# Activity_Recognition_Board_v1_0_MCU.net
KiCad netlist of a schematic drawn in Altium Designer
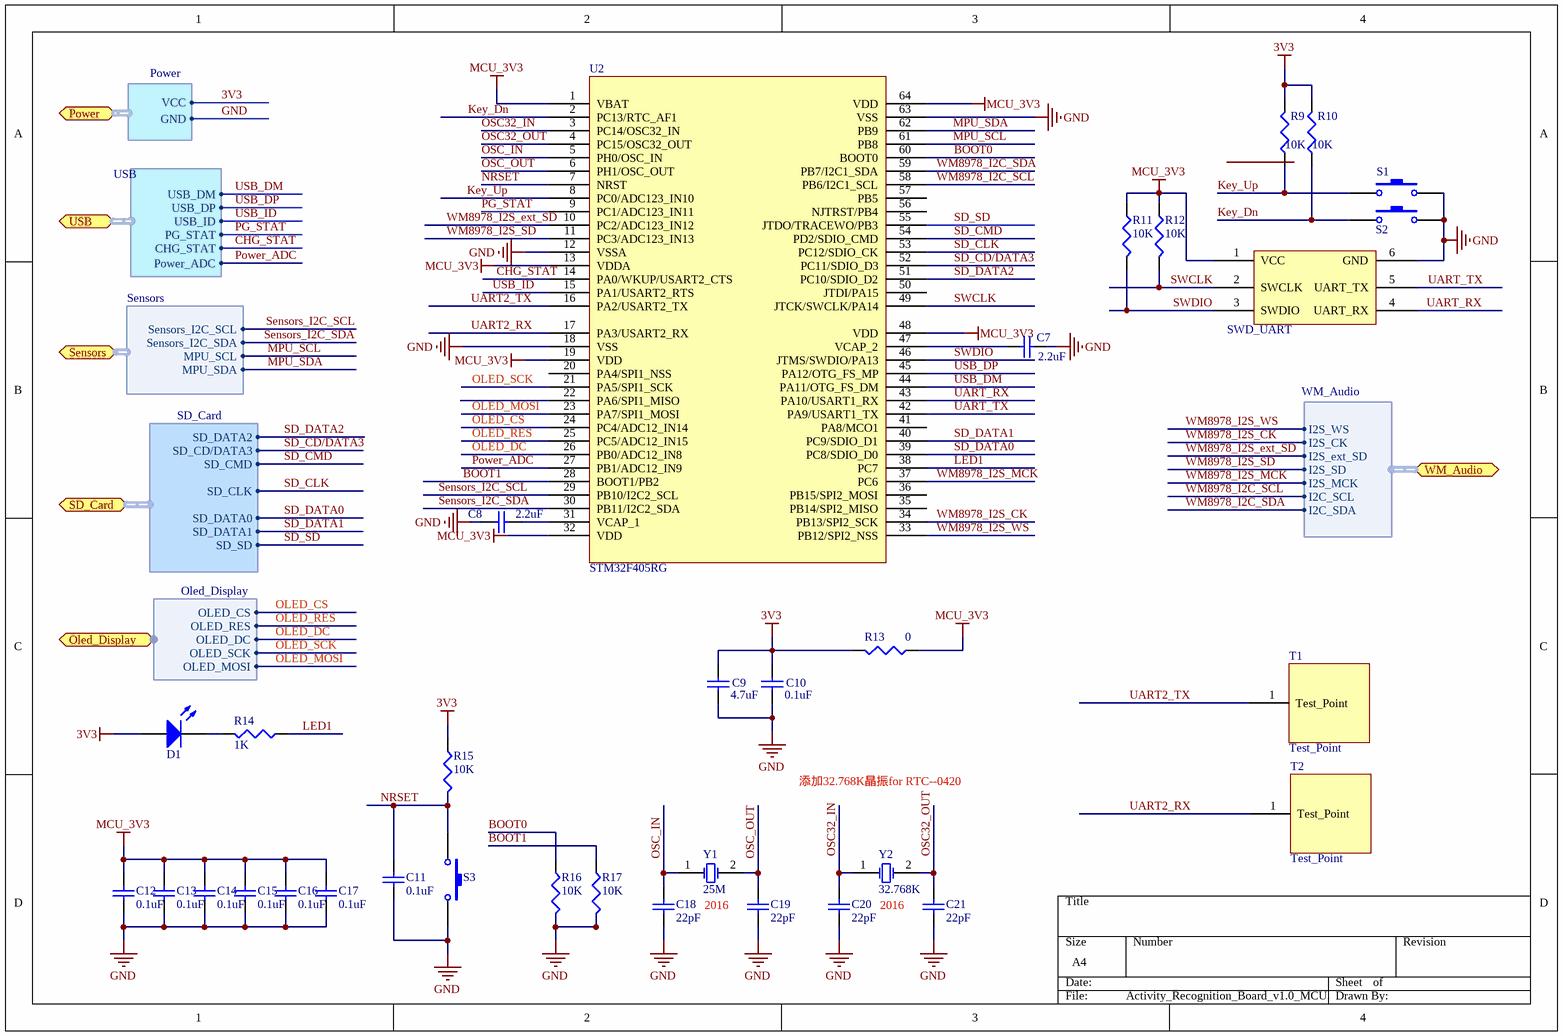
[diagram p0: Activity_Recognition_Board_v1.0_MCU.SchDoc]

(export (version "E")
  (design (tool "Eeschema 10.0.6"))
  (components
    (comp (ref "C7")
      (value "2.2uF")
      (footprint "C0603")
      (description "Capacitor (Semiconductor SIM Model)")
      (fields (field (name "Comment") "Cap semi") (field (name "PUBLISHER") "Altium Limited"))
      (libsource (lib "Miscellaneous Devices") (part "Cap Semi"))
    )
    (comp (ref "C8")
      (value "2.2uF")
      (footprint "C0603")
      (description "Capacitor (Semiconductor SIM Model)")
      (fields (field (name "Comment") "Cap semi") (field (name "PUBLISHER") "Altium Limited"))
      (libsource (lib "Miscellaneous Devices") (part "Cap Semi"))
    )
    (comp (ref "C9")
      (value "4.7uF")
      (footprint "C0603")
      (description "Capacitor (Semiconductor SIM Model)")
      (fields (field (name "Comment") "Cap semi") (field (name "PUBLISHER") "Altium Limited"))
      (libsource (lib "Miscellaneous Devices") (part "Cap Semi"))
    )
    (comp (ref "C10")
      (value "0.1uF")
      (footprint "C0402")
      (description "Capacitor (Semiconductor SIM Model)")
      (fields (field (name "Comment") "Cap semi") (field (name "PUBLISHER") "Altium Limited"))
      (libsource (lib "Miscellaneous Devices") (part "Cap Semi"))
    )
    (comp (ref "C11")
      (value "0.1uF")
      (footprint "C0402")
      (description "Capacitor (Semiconductor SIM Model)")
      (fields (field (name "Comment") "Cap semi") (field (name "PUBLISHER") "Altium Limited"))
      (libsource (lib "Miscellaneous Devices") (part "Cap Semi"))
    )
    (comp (ref "C12")
      (value "0.1uF")
      (footprint "C0402")
      (description "Capacitor (Semiconductor SIM Model)")
      (fields (field (name "Comment") "Cap semi") (field (name "PUBLISHER") "Altium Limited"))
      (libsource (lib "Miscellaneous Devices") (part "Cap Semi"))
    )
    (comp (ref "C13")
      (value "0.1uF")
      (footprint "C0402")
      (description "Capacitor (Semiconductor SIM Model)")
      (fields (field (name "Comment") "Cap semi") (field (name "PUBLISHER") "Altium Limited"))
      (libsource (lib "Miscellaneous Devices") (part "Cap Semi"))
    )
    (comp (ref "C14")
      (value "0.1uF")
      (footprint "C0402")
      (description "Capacitor (Semiconductor SIM Model)")
      (fields (field (name "Comment") "Cap semi") (field (name "PUBLISHER") "Altium Limited"))
      (libsource (lib "Miscellaneous Devices") (part "Cap Semi"))
    )
    (comp (ref "C15")
      (value "0.1uF")
      (footprint "C0402")
      (description "Capacitor (Semiconductor SIM Model)")
      (fields (field (name "Comment") "Cap semi") (field (name "PUBLISHER") "Altium Limited"))
      (libsource (lib "Miscellaneous Devices") (part "Cap Semi"))
    )
    (comp (ref "C16")
      (value "0.1uF")
      (footprint "C0402")
      (description "Capacitor (Semiconductor SIM Model)")
      (fields (field (name "Comment") "Cap semi") (field (name "PUBLISHER") "Altium Limited"))
      (libsource (lib "Miscellaneous Devices") (part "Cap Semi"))
    )
    (comp (ref "C17")
      (value "0.1uF")
      (footprint "C0402")
      (description "Capacitor (Semiconductor SIM Model)")
      (fields (field (name "Comment") "Cap semi") (field (name "PUBLISHER") "Altium Limited"))
      (libsource (lib "Miscellaneous Devices") (part "Cap Semi"))
    )
    (comp (ref "C18")
      (value "22pF")
      (footprint "C0402")
      (description "Capacitor (Semiconductor SIM Model)")
      (fields (field (name "Comment") "Cap semi") (field (name "PUBLISHER") "Altium Limited"))
      (libsource (lib "Miscellaneous Devices") (part "Cap Semi"))
    )
    (comp (ref "C19")
      (value "22pF")
      (footprint "C0402")
      (description "Capacitor (Semiconductor SIM Model)")
      (fields (field (name "Comment") "Cap semi") (field (name "PUBLISHER") "Altium Limited"))
      (libsource (lib "Miscellaneous Devices") (part "Cap Semi"))
    )
    (comp (ref "C20")
      (value "22pF")
      (footprint "C0402")
      (description "Capacitor (Semiconductor SIM Model)")
      (fields (field (name "Comment") "Cap semi") (field (name "PUBLISHER") "Altium Limited"))
      (libsource (lib "Miscellaneous Devices") (part "Cap Semi"))
    )
    (comp (ref "C21")
      (value "22pF")
      (footprint "C0402")
      (description "Capacitor (Semiconductor SIM Model)")
      (fields (field (name "Comment") "Cap semi") (field (name "PUBLISHER") "Altium Limited"))
      (libsource (lib "Miscellaneous Devices") (part "Cap Semi"))
    )
    (comp (ref "D1")
      (value "LED3")
      (footprint "LED0603")
      (description "Typical BLUE SiC LED")
      (fields (field (name "PUBLISHER") "Altium Limited"))
      (libsource (lib "Miscellaneous Devices") (part "LED3"))
    )
    (comp (ref "R9")
      (value "10K")
      (footprint "R0402")
      (description "Resistor")
      (fields (field (name "Comment") "Res3") (field (name "PUBLISHER") "Altium Limited"))
      (libsource (lib "Miscellaneous Devices") (part "Res3"))
    )
    (comp (ref "R10")
      (value "10K")
      (footprint "R0402")
      (description "Resistor")
      (fields (field (name "Comment") "Res3") (field (name "PUBLISHER") "Altium Limited"))
      (libsource (lib "Miscellaneous Devices") (part "Res3"))
    )
    (comp (ref "R11")
      (value "10K")
      (footprint "R0402")
      (description "Resistor")
      (fields (field (name "Comment") "Res3") (field (name "PUBLISHER") "Altium Limited"))
      (libsource (lib "Miscellaneous Devices") (part "Res3"))
    )
    (comp (ref "R12")
      (value "10K")
      (footprint "R0402")
      (description "Resistor")
      (fields (field (name "Comment") "Res3") (field (name "PUBLISHER") "Altium Limited"))
      (libsource (lib "Miscellaneous Devices") (part "Res3"))
    )
    (comp (ref "R13")
      (value "0")
      (footprint "R0603")
      (description "Resistor")
      (fields (field (name "Comment") "Res3") (field (name "PUBLISHER") "Altium Limited"))
      (libsource (lib "Miscellaneous Devices") (part "Res3"))
    )
    (comp (ref "R14")
      (value "1K")
      (footprint "R0402")
      (description "Resistor")
      (fields (field (name "Comment") "Res3") (field (name "PUBLISHER") "Altium Limited"))
      (libsource (lib "Miscellaneous Devices") (part "Res3"))
    )
    (comp (ref "R15")
      (value "10K")
      (footprint "R0402")
      (description "Resistor")
      (fields (field (name "Comment") "Res3") (field (name "PUBLISHER") "Altium Limited"))
      (libsource (lib "Miscellaneous Devices") (part "Res3"))
    )
    (comp (ref "R16")
      (value "10K")
      (footprint "R0402")
      (description "Resistor")
      (fields (field (name "Comment") "Res3") (field (name "PUBLISHER") "Altium Limited"))
      (libsource (lib "Miscellaneous Devices") (part "Res3"))
    )
    (comp (ref "R17")
      (value "10K")
      (footprint "R0402")
      (description "Resistor")
      (fields (field (name "Comment") "Res3") (field (name "PUBLISHER") "Altium Limited"))
      (libsource (lib "Miscellaneous Devices") (part "Res3"))
    )
    (comp (ref "S1")
      (value "SW-PB")
      (footprint "MP34")
      (description "Switch")
      (fields (field (name "PUBLISHER") "Altium Limited"))
      (libsource (lib "Miscellaneous Devices") (part "SW-PB"))
    )
    (comp (ref "S2")
      (value "SW-PB")
      (footprint "MP34")
      (description "Switch")
      (fields (field (name "PUBLISHER") "Altium Limited"))
      (libsource (lib "Miscellaneous Devices") (part "SW-PB"))
    )
    (comp (ref "S3")
      (value "SW-PB")
      (footprint "MP34")
      (description "Switch")
      (fields (field (name "PUBLISHER") "Altium Limited"))
      (libsource (lib "Miscellaneous Devices") (part "SW-PB"))
    )
    (comp (ref "SWD_UART1")
      (value "SWD_UART")
      (footprint "FFC_6")
      (libsource (lib "Activity_Recognition_Board") (part "SWD_UART"))
    )
    (comp (ref "T1")
      (value "Test_Point")
      (footprint "Test_Point")
      (libsource (lib "Activity_Recognition_Board") (part "Test_Point"))
    )
    (comp (ref "T2")
      (value "Test_Point")
      (footprint "Test_Point")
      (libsource (lib "Activity_Recognition_Board") (part "Test_Point"))
    )
    (comp (ref "U2")
      (value "STM32F405RG")
      (footprint "LQFP64")
      (libsource (lib "Schlib1_GuJun") (part "STM32F405RG"))
    )
    (comp (ref "Y1")
      (value "25M")
      (footprint "3225")
      (description "Crystal Oscillator")
      (fields (field (name "PUBLISHER") "Altium Limited"))
      (libsource (lib "Miscellaneous Devices") (part "XTAL"))
    )
    (comp (ref "Y2")
      (value "32.768K")
      (footprint "3215")
      (description "Crystal Oscillator")
      (fields (field (name "PUBLISHER") "Altium Limited"))
      (libsource (lib "Miscellaneous Devices") (part "XTAL"))
    )
  )
  (nets
    (net (code "7") (name "/BOOT0") (class "Default")
      (node (ref "R16") (pin "1") (pinfunction "1_1") (pintype "passive"))
      (node (ref "U2") (pin "60") (pinfunction "BOOT0_60") (pintype "passive"))
    )
    (net (code "8") (name "/BOOT1") (class "Default")
      (node (ref "R17") (pin "1") (pinfunction "1_1") (pintype "passive"))
      (node (ref "U2") (pin "28") (pinfunction "BOOT1/PB2_28") (pintype "passive"))
    )
    (net (code "9") (name "/CHG_STAT") (class "Default")
      (node (ref "U2") (pin "14") (pinfunction "PA0/WKUP/USART2_CTS_14") (pintype "passive"))
    )
    (net (code "10") (name "/Key_Dn") (class "Default")
      (node (ref "R10") (pin "1") (pinfunction "1_1") (pintype "passive"))
      (node (ref "S2") (pin "1") (pinfunction "1_1") (pintype "passive"))
      (node (ref "U2") (pin "2") (pinfunction "PC13/RTC_AF1_2") (pintype "passive"))
    )
    (net (code "11") (name "/Key_Up") (class "Default")
      (node (ref "R9") (pin "1") (pinfunction "1_1") (pintype "passive"))
      (node (ref "S1") (pin "1") (pinfunction "1_1") (pintype "passive"))
      (node (ref "U2") (pin "8") (pinfunction "PC0/ADC123_IN10_8") (pintype "passive"))
    )
    (net (code "12") (name "/LED1") (class "Default")
      (node (ref "R14") (pin "1") (pinfunction "1_1") (pintype "passive"))
      (node (ref "U2") (pin "38") (pinfunction "PC7_38") (pintype "passive"))
    )
    (net (code "13") (name "/MPU_SCL") (class "Default")
      (node (ref "U2") (pin "61") (pinfunction "PB8_61") (pintype "passive"))
    )
    (net (code "14") (name "/MPU_SDA") (class "Default")
      (node (ref "U2") (pin "62") (pinfunction "PB9_62") (pintype "passive"))
    )
    (net (code "15") (name "/NRSET") (class "Default")
      (node (ref "C11") (pin "2") (pinfunction "2_2") (pintype "passive"))
      (node (ref "R15") (pin "2") (pinfunction "2_2") (pintype "passive"))
      (node (ref "S3") (pin "1") (pinfunction "1_1") (pintype "passive"))
      (node (ref "U2") (pin "7") (pinfunction "NRST_7") (pintype "passive"))
    )
    (net (code "16") (name "/OLED_CS") (class "Default")
      (node (ref "U2") (pin "24") (pinfunction "PC4/ADC12_IN14_24") (pintype "passive"))
    )
    (net (code "17") (name "/OLED_DC") (class "Default")
      (node (ref "U2") (pin "26") (pinfunction "PB0/ADC12_IN8_26") (pintype "passive"))
    )
    (net (code "18") (name "/OLED_MOSI") (class "Default")
      (node (ref "U2") (pin "23") (pinfunction "PA7/SPI1_MOSI_23") (pintype "passive"))
    )
    (net (code "19") (name "/OLED_RES") (class "Default")
      (node (ref "U2") (pin "25") (pinfunction "PC5/ADC12_IN15_25") (pintype "passive"))
    )
    (net (code "20") (name "/OLED_SCK") (class "Default")
      (node (ref "U2") (pin "21") (pinfunction "PA5/SPI1_SCK_21") (pintype "passive"))
    )
    (net (code "21") (name "/OSC32_IN") (class "Default")
      (node (ref "C20") (pin "2") (pinfunction "2_2") (pintype "passive"))
      (node (ref "U2") (pin "3") (pinfunction "PC14/OSC32_IN_3") (pintype "passive"))
      (node (ref "Y2") (pin "1") (pinfunction "OSC1_1") (pintype "passive"))
    )
    (net (code "22") (name "/OSC32_OUT") (class "Default")
      (node (ref "C21") (pin "2") (pinfunction "2_2") (pintype "passive"))
      (node (ref "U2") (pin "4") (pinfunction "PC15/OSC32_OUT_4") (pintype "passive"))
      (node (ref "Y2") (pin "2") (pinfunction "OSC2_2") (pintype "passive"))
    )
    (net (code "23") (name "/OSC_IN") (class "Default")
      (node (ref "C18") (pin "2") (pinfunction "2_2") (pintype "passive"))
      (node (ref "U2") (pin "5") (pinfunction "PH0/OSC_IN_5") (pintype "passive"))
      (node (ref "Y1") (pin "1") (pinfunction "OSC1_1") (pintype "passive"))
    )
    (net (code "24") (name "/OSC_OUT") (class "Default")
      (node (ref "C19") (pin "2") (pinfunction "2_2") (pintype "passive"))
      (node (ref "U2") (pin "6") (pinfunction "PH1/OSC_OUT_6") (pintype "passive"))
      (node (ref "Y1") (pin "2") (pinfunction "OSC2_2") (pintype "passive"))
    )
    (net (code "25") (name "/PG_STAT") (class "Default")
      (node (ref "U2") (pin "9") (pinfunction "PC1/ADC123_IN11_9") (pintype "passive"))
    )
    (net (code "26") (name "/Power_ADC") (class "Default")
      (node (ref "U2") (pin "27") (pinfunction "PB1/ADC12_IN9_27") (pintype "passive"))
    )
    (net (code "27") (name "/SD_CD{slash}DATA3") (class "Default")
      (node (ref "U2") (pin "52") (pinfunction "PC11/SDIO_D3_52") (pintype "passive"))
    )
    (net (code "28") (name "/SD_CLK") (class "Default")
      (node (ref "U2") (pin "53") (pinfunction "PC12/SDIO_CK_53") (pintype "passive"))
    )
    (net (code "29") (name "/SD_CMD") (class "Default")
      (node (ref "U2") (pin "54") (pinfunction "PD2/SDIO_CMD_54") (pintype "passive"))
    )
    (net (code "30") (name "/SD_DATA0") (class "Default")
      (node (ref "U2") (pin "39") (pinfunction "PC8/SDIO_D0_39") (pintype "passive"))
    )
    (net (code "31") (name "/SD_DATA1") (class "Default")
      (node (ref "U2") (pin "40") (pinfunction "PC9/SDIO_D1_40") (pintype "passive"))
    )
    (net (code "32") (name "/SD_DATA2") (class "Default")
      (node (ref "U2") (pin "51") (pinfunction "PC10/SDIO_D2_51") (pintype "passive"))
    )
    (net (code "33") (name "/SD_SD") (class "Default")
      (node (ref "U2") (pin "55") (pinfunction "JTDO/TRACEWO/PB3_55") (pintype "passive"))
    )
    (net (code "34") (name "/SWCLK") (class "Default")
      (node (ref "R12") (pin "2") (pinfunction "2_2") (pintype "passive"))
      (node (ref "SWD_UART1") (pin "2") (pinfunction "SWCLK_2") (pintype "passive"))
      (node (ref "U2") (pin "49") (pinfunction "JTCK/SWCLK/PA14_49") (pintype "passive"))
    )
    (net (code "35") (name "/SWDIO") (class "Default")
      (node (ref "R11") (pin "2") (pinfunction "2_2") (pintype "passive"))
      (node (ref "SWD_UART1") (pin "3") (pinfunction "SWDIO_3") (pintype "passive"))
      (node (ref "U2") (pin "46") (pinfunction "JTMS/SWDIO/PA13_46") (pintype "passive"))
    )
    (net (code "36") (name "/Sensors_I2C_SCL") (class "Default")
      (node (ref "U2") (pin "29") (pinfunction "PB10/I2C2_SCL_29") (pintype "passive"))
    )
    (net (code "37") (name "/Sensors_I2C_SDA") (class "Default")
      (node (ref "U2") (pin "30") (pinfunction "PB11/I2C2_SDA_30") (pintype "passive"))
    )
    (net (code "38") (name "/UART2_RX") (class "Default")
      (node (ref "T2") (pin "1") (pinfunction "Test_Point_1") (pintype "passive"))
      (node (ref "U2") (pin "17") (pinfunction "PA3/USART2_RX_17") (pintype "passive"))
    )
    (net (code "39") (name "/UART2_TX") (class "Default")
      (node (ref "T1") (pin "1") (pinfunction "Test_Point_1") (pintype "passive"))
      (node (ref "U2") (pin "16") (pinfunction "PA2/USART2_TX_16") (pintype "passive"))
    )
    (net (code "40") (name "/UART_RX") (class "Default")
      (node (ref "SWD_UART1") (pin "4") (pinfunction "UART_RX_4") (pintype "passive"))
      (node (ref "U2") (pin "43") (pinfunction "PA10/USART1_RX_43") (pintype "passive"))
    )
    (net (code "41") (name "/UART_TX") (class "Default")
      (node (ref "SWD_UART1") (pin "5") (pinfunction "UART_TX_5") (pintype "passive"))
      (node (ref "U2") (pin "42") (pinfunction "PA9/USART1_TX_42") (pintype "passive"))
    )
    (net (code "42") (name "/USB_DM") (class "Default")
      (node (ref "U2") (pin "44") (pinfunction "PA11/OTG_FS_DM_44") (pintype "passive"))
    )
    (net (code "43") (name "/USB_DP") (class "Default")
      (node (ref "U2") (pin "45") (pinfunction "PA12/OTG_FS_MP_45") (pintype "passive"))
    )
    (net (code "44") (name "/USB_ID") (class "Default")
      (node (ref "U2") (pin "15") (pinfunction "PA1/USART2_RTS_15") (pintype "passive"))
    )
    (net (code "45") (name "/WM8978_I2C_SCL") (class "Default")
      (node (ref "U2") (pin "58") (pinfunction "PB6/I2C1_SCL_58") (pintype "passive"))
    )
    (net (code "46") (name "/WM8978_I2C_SDA") (class "Default")
      (node (ref "U2") (pin "59") (pinfunction "PB7/I2C1_SDA_59") (pintype "passive"))
    )
    (net (code "47") (name "/WM8978_I2S_CK") (class "Default")
      (node (ref "U2") (pin "34") (pinfunction "PB13/SPI2_SCK_34") (pintype "passive"))
    )
    (net (code "48") (name "/WM8978_I2S_MCK") (class "Default")
      (node (ref "U2") (pin "37") (pinfunction "PC6_37") (pintype "passive"))
    )
    (net (code "49") (name "/WM8978_I2S_SD") (class "Default")
      (node (ref "U2") (pin "11") (pinfunction "PC3/ADC123_IN13_11") (pintype "passive"))
    )
    (net (code "50") (name "/WM8978_I2S_WS") (class "Default")
      (node (ref "U2") (pin "33") (pinfunction "PB12/SPI2_NSS_33") (pintype "passive"))
    )
    (net (code "51") (name "/WM8978_I2S_ext_SD") (class "Default")
      (node (ref "U2") (pin "10") (pinfunction "PC2/ADC123_IN12_10") (pintype "passive"))
    )
    (net (code "58") (name "3V3") (class "Default")
      (node (ref "C10") (pin "1") (pinfunction "1_1") (pintype "passive"))
      (node (ref "C9") (pin "1") (pinfunction "1_1") (pintype "passive"))
      (node (ref "D1") (pin "1") (pinfunction "A_1") (pintype "passive"))
      (node (ref "R10") (pin "2") (pinfunction "2_2") (pintype "passive"))
      (node (ref "R13") (pin "2") (pinfunction "2_2") (pintype "passive"))
      (node (ref "R15") (pin "1") (pinfunction "1_1") (pintype "passive"))
      (node (ref "R9") (pin "2") (pinfunction "2_2") (pintype "passive"))
    )
    (net (code "59") (name "GND") (class "Default")
      (node (ref "C10") (pin "2") (pinfunction "2_2") (pintype "passive"))
      (node (ref "C11") (pin "1") (pinfunction "1_1") (pintype "passive"))
      (node (ref "C12") (pin "1") (pinfunction "1_1") (pintype "passive"))
      (node (ref "C13") (pin "1") (pinfunction "1_1") (pintype "passive"))
      (node (ref "C14") (pin "1") (pinfunction "1_1") (pintype "passive"))
      (node (ref "C15") (pin "1") (pinfunction "1_1") (pintype "passive"))
      (node (ref "C16") (pin "1") (pinfunction "1_1") (pintype "passive"))
      (node (ref "C17") (pin "1") (pinfunction "1_1") (pintype "passive"))
      (node (ref "C18") (pin "1") (pinfunction "1_1") (pintype "passive"))
      (node (ref "C19") (pin "1") (pinfunction "1_1") (pintype "passive"))
      (node (ref "C20") (pin "1") (pinfunction "1_1") (pintype "passive"))
      (node (ref "C21") (pin "1") (pinfunction "1_1") (pintype "passive"))
      (node (ref "C7") (pin "1") (pinfunction "1_1") (pintype "passive"))
      (node (ref "C8") (pin "2") (pinfunction "2_2") (pintype "passive"))
      (node (ref "C9") (pin "2") (pinfunction "2_2") (pintype "passive"))
      (node (ref "R16") (pin "2") (pinfunction "2_2") (pintype "passive"))
      (node (ref "R17") (pin "2") (pinfunction "2_2") (pintype "passive"))
      (node (ref "S1") (pin "2") (pinfunction "2_2") (pintype "passive"))
      (node (ref "S2") (pin "2") (pinfunction "2_2") (pintype "passive"))
      (node (ref "S3") (pin "2") (pinfunction "2_2") (pintype "passive"))
      (node (ref "SWD_UART1") (pin "6") (pinfunction "GND_6") (pintype "passive"))
      (node (ref "U2") (pin "12") (pinfunction "VSSA_12") (pintype "passive"))
      (node (ref "U2") (pin "18") (pinfunction "VSS_18") (pintype "passive"))
      (node (ref "U2") (pin "63") (pinfunction "VSS_63") (pintype "passive"))
    )
    (net (code "60") (name "MCU_3V3") (class "Default")
      (node (ref "C12") (pin "2") (pinfunction "2_2") (pintype "passive"))
      (node (ref "C13") (pin "2") (pinfunction "2_2") (pintype "passive"))
      (node (ref "C14") (pin "2") (pinfunction "2_2") (pintype "passive"))
      (node (ref "C15") (pin "2") (pinfunction "2_2") (pintype "passive"))
      (node (ref "C16") (pin "2") (pinfunction "2_2") (pintype "passive"))
      (node (ref "C17") (pin "2") (pinfunction "2_2") (pintype "passive"))
      (node (ref "R11") (pin "1") (pinfunction "1_1") (pintype "passive"))
      (node (ref "R12") (pin "1") (pinfunction "1_1") (pintype "passive"))
      (node (ref "R13") (pin "1") (pinfunction "1_1") (pintype "passive"))
      (node (ref "SWD_UART1") (pin "1") (pinfunction "VCC_1") (pintype "passive"))
      (node (ref "U2") (pin "1") (pinfunction "VBAT_1") (pintype "passive"))
      (node (ref "U2") (pin "13") (pinfunction "VDDA_13") (pintype "passive"))
      (node (ref "U2") (pin "19") (pinfunction "VDD_19") (pintype "passive"))
      (node (ref "U2") (pin "32") (pinfunction "VDD_32") (pintype "passive"))
      (node (ref "U2") (pin "48") (pinfunction "VDD_48") (pintype "passive"))
      (node (ref "U2") (pin "64") (pinfunction "VDD_64") (pintype "passive"))
    )
    (net (code "61") (name "Net-(D1-K)") (class "Default")
      (node (ref "D1") (pin "2") (pinfunction "K_2") (pintype "passive"))
      (node (ref "R14") (pin "2") (pinfunction "2_2") (pintype "passive"))
    )
    (net (code "62") (name "Net-(U2-VCAP_1)") (class "Default")
      (node (ref "C8") (pin "1") (pinfunction "1_1") (pintype "passive"))
      (node (ref "U2") (pin "31") (pinfunction "VCAP_1_31") (pintype "passive"))
    )
    (net (code "63") (name "Net-(U2-VCAP_2)") (class "Default")
      (node (ref "C7") (pin "2") (pinfunction "2_2") (pintype "passive"))
      (node (ref "U2") (pin "47") (pinfunction "VCAP_2_47") (pintype "passive"))
    )
    (net (code "64") (name "unconnected-(U2-JTDI{slash}PA15-Pad50)") (class "Default")
      (node (ref "U2") (pin "50") (pinfunction "JTDI/PA15_50") (pintype "passive"))
    )
    (net (code "65") (name "unconnected-(U2-NJTRST{slash}PB4-Pad56)") (class "Default")
      (node (ref "U2") (pin "56") (pinfunction "NJTRST/PB4_56") (pintype "passive"))
    )
    (net (code "66") (name "unconnected-(U2-PA4{slash}SPI1_NSS-Pad20)") (class "Default")
      (node (ref "U2") (pin "20") (pinfunction "PA4/SPI1_NSS_20") (pintype "passive"))
    )
    (net (code "67") (name "unconnected-(U2-PA6{slash}SPI1_MISO-Pad22)") (class "Default")
      (node (ref "U2") (pin "22") (pinfunction "PA6/SPI1_MISO_22") (pintype "passive"))
    )
    (net (code "68") (name "unconnected-(U2-PA8{slash}MCO1-Pad41)") (class "Default")
      (node (ref "U2") (pin "41") (pinfunction "PA8/MCO1_41") (pintype "passive"))
    )
    (net (code "69") (name "unconnected-(U2-PB5-Pad57)") (class "Default")
      (node (ref "U2") (pin "57") (pinfunction "PB5_57") (pintype "passive"))
    )
    (net (code "70") (name "unconnected-(U2-PB14{slash}SPI2_MISO-Pad35)") (class "Default")
      (node (ref "U2") (pin "35") (pinfunction "PB14/SPI2_MISO_35") (pintype "passive"))
    )
    (net (code "71") (name "unconnected-(U2-PB15{slash}SPI2_MOSI-Pad36)") (class "Default")
      (node (ref "U2") (pin "36") (pinfunction "PB15/SPI2_MOSI_36") (pintype "passive"))
    )
  )
)
